# Filter_Capacitors_-_Signal_IoT.net
KiCad netlist of a schematic drawn in Altium Designer
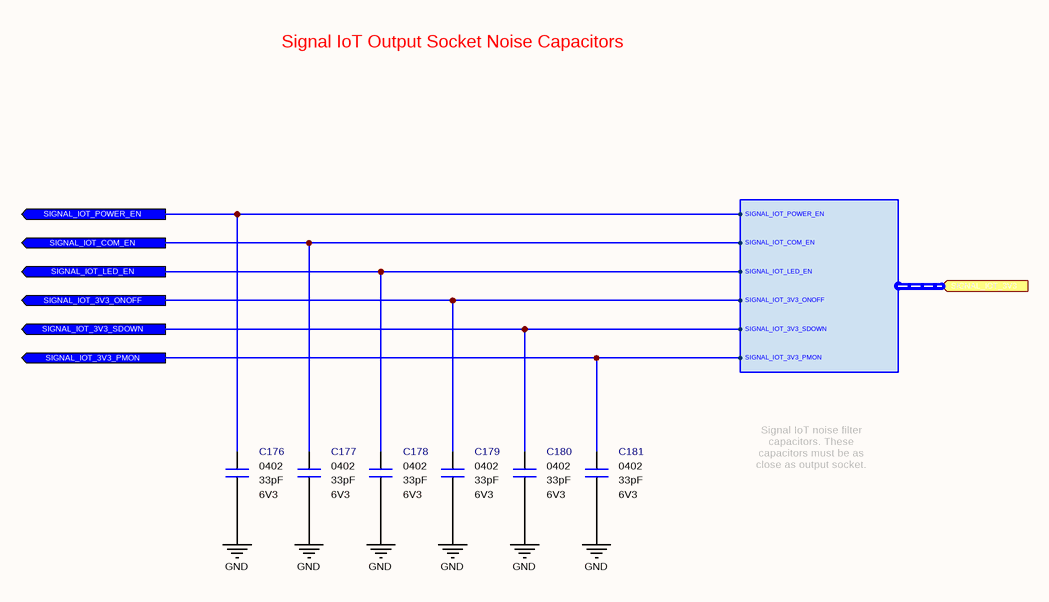
[diagram p0: Filter Capacitors - Signal IoT.SchDoc]

(export (version "E")
  (design (tool "Eeschema 10.0.6"))
  (components
    (comp (ref "C176")
      (value "33pF")
      (footprint "CAPACITOR_0402")
      (description "Capacitor - 33pF [0402] (Ceramic)")
      (fields
        (field (name "TOLERANCE") "10%")
        (field (name "CASE") "0402")
        (field (name "VOLTAGE") "6V3")
        (field (name "MANUFACTURER PART NUMBER") "C0402C330J9RACAUTO")
      )
      (libsource (lib "Ovoo_Library") (part "Capacitor - 33pF [0402-6V3]"))
    )
    (comp (ref "C177")
      (value "33pF")
      (footprint "CAPACITOR_0402")
      (description "Capacitor - 33pF [0402] (Ceramic)")
      (fields
        (field (name "TOLERANCE") "10%")
        (field (name "CASE") "0402")
        (field (name "VOLTAGE") "6V3")
        (field (name "MANUFACTURER PART NUMBER") "C0402C330J9RACAUTO")
      )
      (libsource (lib "Ovoo_Library") (part "Capacitor - 33pF [0402-6V3]"))
    )
    (comp (ref "C178")
      (value "33pF")
      (footprint "CAPACITOR_0402")
      (description "Capacitor - 33pF [0402] (Ceramic)")
      (fields
        (field (name "TOLERANCE") "10%")
        (field (name "CASE") "0402")
        (field (name "VOLTAGE") "6V3")
        (field (name "MANUFACTURER PART NUMBER") "C0402C330J9RACAUTO")
      )
      (libsource (lib "Ovoo_Library") (part "Capacitor - 33pF [0402-6V3]"))
    )
    (comp (ref "C179")
      (value "33pF")
      (footprint "CAPACITOR_0402")
      (description "Capacitor - 33pF [0402] (Ceramic)")
      (fields
        (field (name "TOLERANCE") "10%")
        (field (name "CASE") "0402")
        (field (name "VOLTAGE") "6V3")
        (field (name "MANUFACTURER PART NUMBER") "C0402C330J9RACAUTO")
      )
      (libsource (lib "Ovoo_Library") (part "Capacitor - 33pF [0402-6V3]"))
    )
    (comp (ref "C180")
      (value "33pF")
      (footprint "CAPACITOR_0402")
      (description "Capacitor - 33pF [0402] (Ceramic)")
      (fields
        (field (name "TOLERANCE") "10%")
        (field (name "CASE") "0402")
        (field (name "VOLTAGE") "6V3")
        (field (name "MANUFACTURER PART NUMBER") "C0402C330J9RACAUTO")
      )
      (libsource (lib "Ovoo_Library") (part "Capacitor - 33pF [0402-6V3]"))
    )
    (comp (ref "C181")
      (value "33pF")
      (footprint "CAPACITOR_0402")
      (description "Capacitor - 33pF [0402] (Ceramic)")
      (fields
        (field (name "TOLERANCE") "10%")
        (field (name "CASE") "0402")
        (field (name "VOLTAGE") "6V3")
        (field (name "MANUFACTURER PART NUMBER") "C0402C330J9RACAUTO")
      )
      (libsource (lib "Ovoo_Library") (part "Capacitor - 33pF [0402-6V3]"))
    )
  )
  (nets
    (net (code "2") (name "/SIGNAL_IOT_3V3_ONOFF") (class "Default")
      (node (ref "C179") (pin "2") (pinfunction "2_2") (pintype "passive"))
    )
    (net (code "3") (name "/SIGNAL_IOT_3V3_PMON") (class "Default")
      (node (ref "C181") (pin "2") (pinfunction "2_2") (pintype "passive"))
    )
    (net (code "4") (name "/SIGNAL_IOT_3V3_SDOWN") (class "Default")
      (node (ref "C180") (pin "2") (pinfunction "2_2") (pintype "passive"))
    )
    (net (code "5") (name "/SIGNAL_IOT_COM_EN") (class "Default")
      (node (ref "C177") (pin "2") (pinfunction "2_2") (pintype "passive"))
    )
    (net (code "6") (name "/SIGNAL_IOT_LED_EN") (class "Default")
      (node (ref "C178") (pin "2") (pinfunction "2_2") (pintype "passive"))
    )
    (net (code "7") (name "/SIGNAL_IOT_POWER_EN") (class "Default")
      (node (ref "C176") (pin "2") (pinfunction "2_2") (pintype "passive"))
    )
    (net (code "9") (name "GND") (class "Default")
      (node (ref "C176") (pin "1") (pinfunction "1_1") (pintype "passive"))
      (node (ref "C177") (pin "1") (pinfunction "1_1") (pintype "passive"))
      (node (ref "C178") (pin "1") (pinfunction "1_1") (pintype "passive"))
      (node (ref "C179") (pin "1") (pinfunction "1_1") (pintype "passive"))
      (node (ref "C180") (pin "1") (pinfunction "1_1") (pintype "passive"))
      (node (ref "C181") (pin "1") (pinfunction "1_1") (pintype "passive"))
    )
  )
)
